# Western_Aero_2020.net
KiCad netlist of a schematic drawn in EAGLE
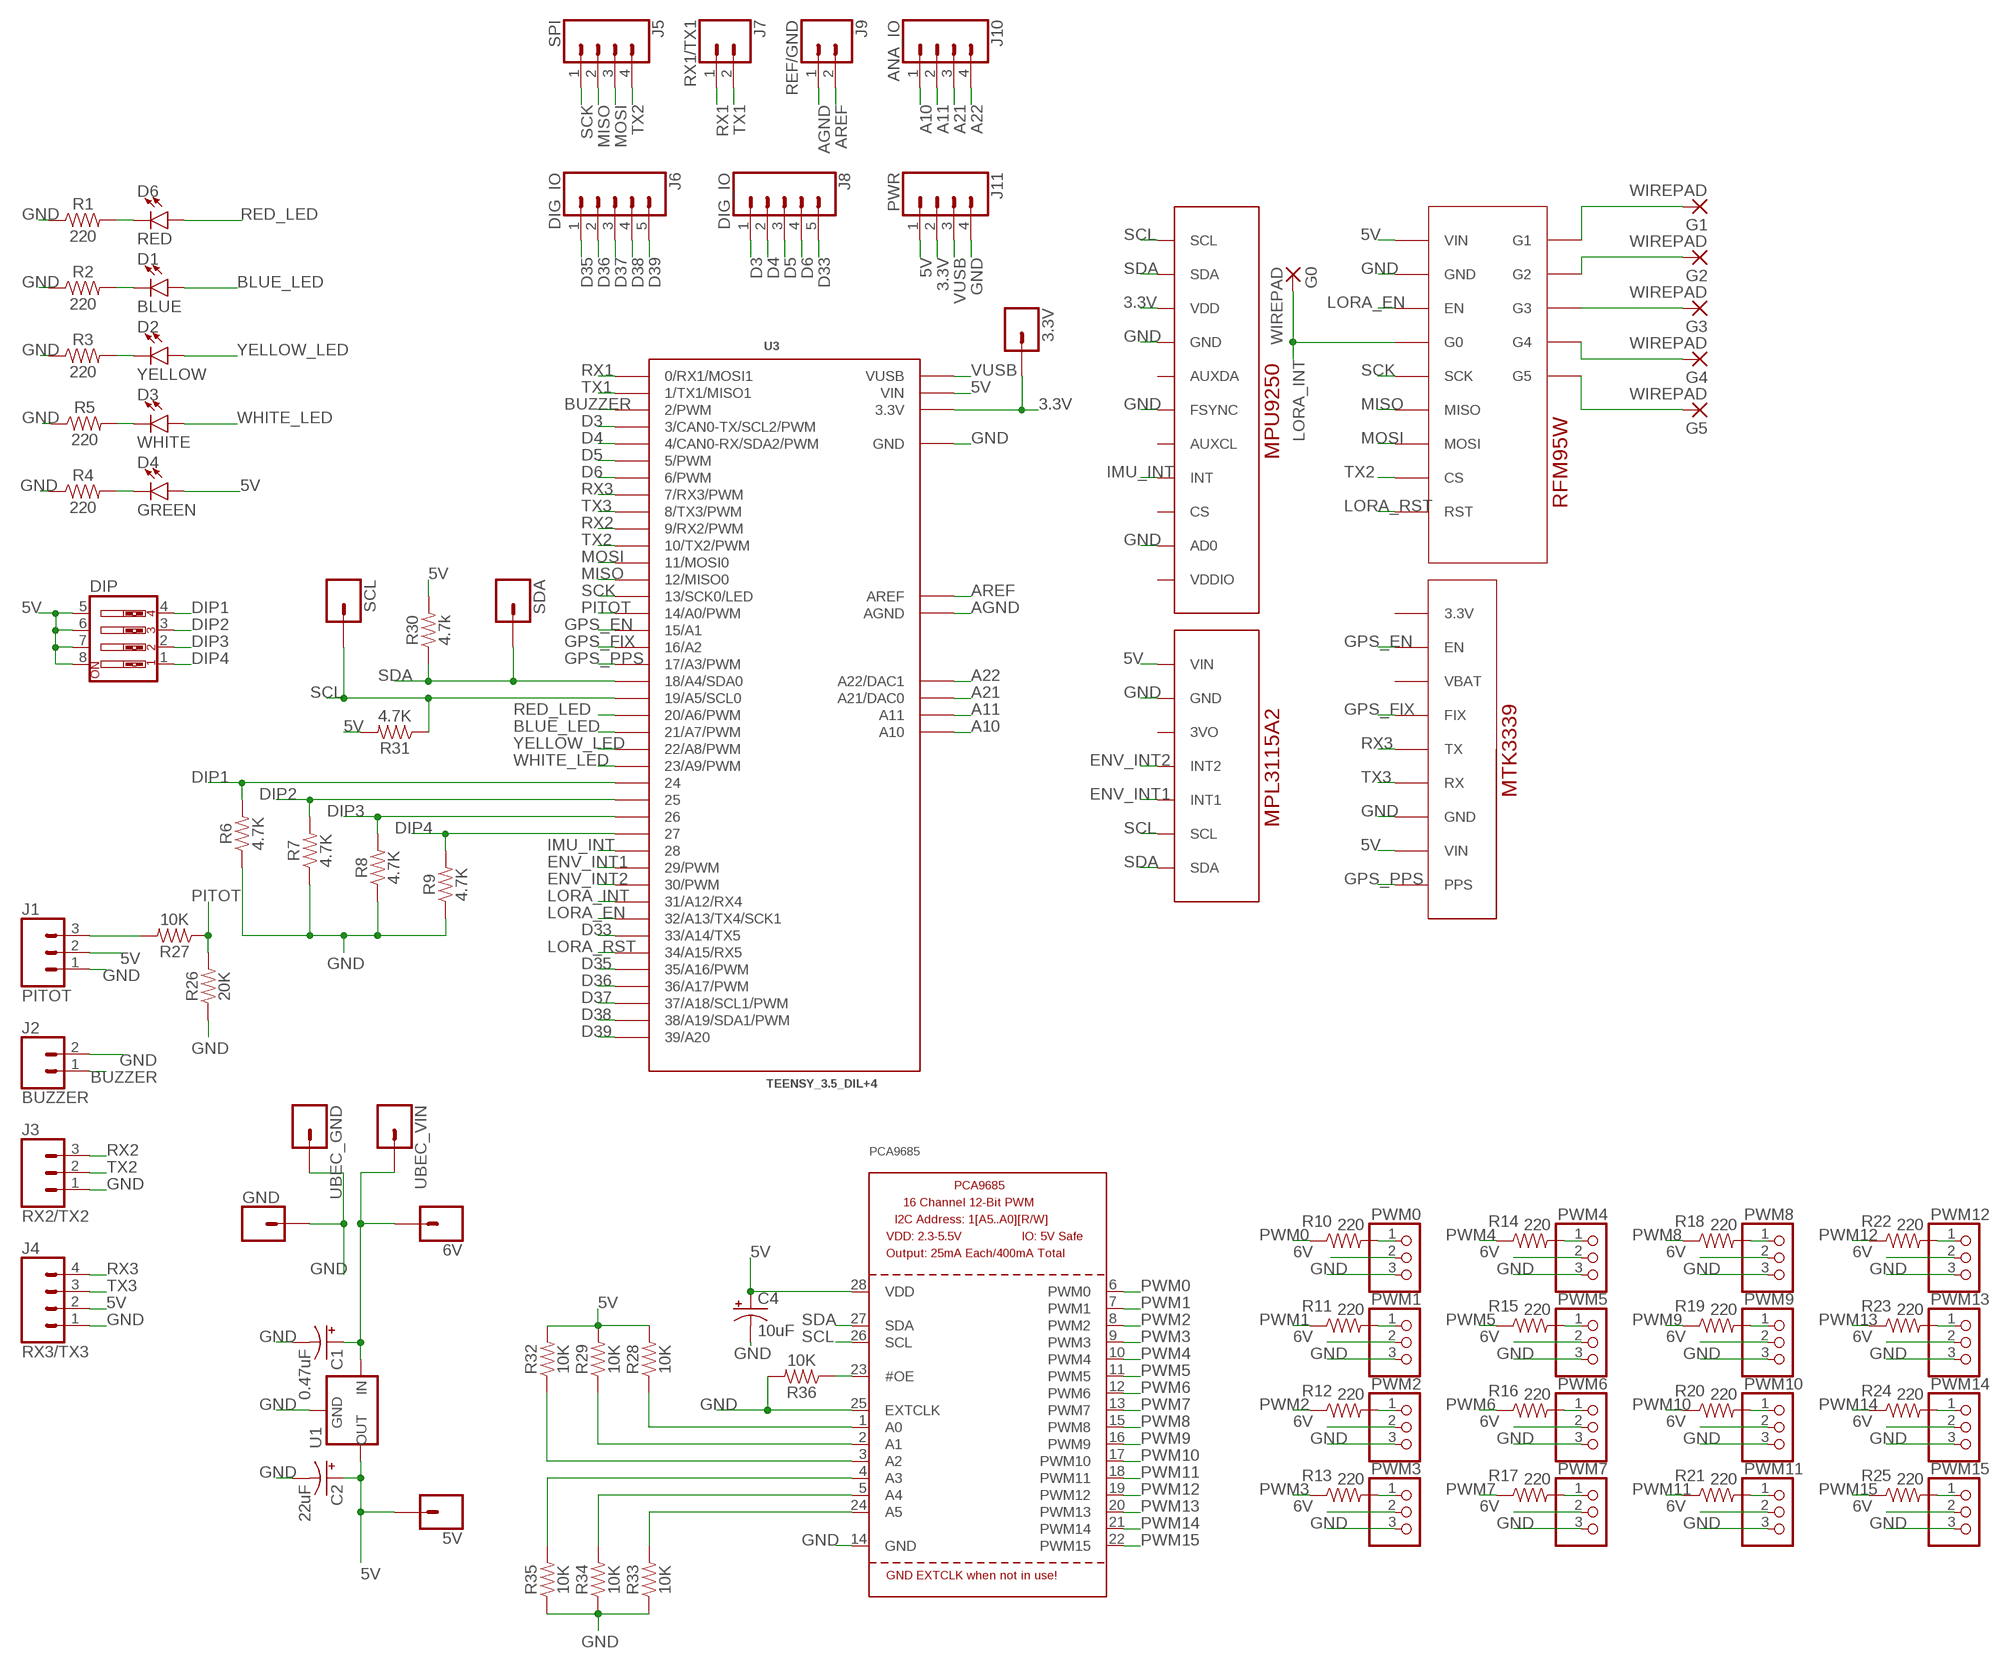
[diagram p0: schematic, sheet 1]

(export (version "E")
  (design (tool "Eeschema 10.0.6"))
  (components
    (comp (ref "3.3V")
      (value "CONN_01")
      (footprint "eagle-import:1X01")
      (libsource (lib "eagle-import") (part "CONN_01"))
    )
    (comp (ref "5V")
      (value "CONN_01")
      (footprint "eagle-import:1X01")
      (libsource (lib "eagle-import") (part "CONN_01"))
    )
    (comp (ref "6V")
      (value "CONN_01")
      (footprint "eagle-import:1X01")
      (libsource (lib "eagle-import") (part "CONN_01"))
    )
    (comp (ref "C1")
      (value "0.47uF")
      (footprint "eagle-import:CPOL-RADIAL-2.5MM-5MM")
      (libsource (lib "eagle-import") (part "10UF-POLAR-RADIAL-2.5MM-25V-20%"))
    )
    (comp (ref "C2")
      (value "22uF")
      (footprint "eagle-import:CPOL-RADIAL-2.5MM-5MM")
      (libsource (lib "eagle-import") (part "10UF-POLAR-RADIAL-2.5MM-25V-20%"))
    )
    (comp (ref "C4")
      (value "10uF")
      (footprint "eagle-import:CPOL-RADIAL-2.5MM-5MM")
      (libsource (lib "eagle-import") (part "10UF-POLAR-RADIAL-2.5MM-25V-20%"))
    )
    (comp (ref "D1")
      (value "BLUE")
      (footprint "eagle-import:LED_5MM")
      (libsource (lib "eagle-import") (part "LED5MM"))
    )
    (comp (ref "D2")
      (value "YELLOW")
      (footprint "eagle-import:LED_5MM")
      (libsource (lib "eagle-import") (part "LED5MM"))
    )
    (comp (ref "D3")
      (value "WHITE")
      (footprint "eagle-import:LED_5MM")
      (libsource (lib "eagle-import") (part "LED5MM"))
    )
    (comp (ref "D4")
      (value "GREEN")
      (footprint "eagle-import:LED_5MM")
      (libsource (lib "eagle-import") (part "LED5MM"))
    )
    (comp (ref "D6")
      (value "RED")
      (footprint "eagle-import:LED_5MM")
      (libsource (lib "eagle-import") (part "LED5MM"))
    )
    (comp (ref "DIP")
      (value "SW_DIP-4")
      (footprint "eagle-import:EDG-04")
      (libsource (lib "eagle-import") (part "SW_DIP-4"))
    )
    (comp (ref "G0")
      (value "WIREPAD")
      (footprint "eagle-import:2,15_1,0")
      (libsource (lib "eagle-import") (part "WIREPAD2,15/1,0"))
    )
    (comp (ref "G1")
      (value "WIREPAD")
      (footprint "eagle-import:2,15_1,0")
      (libsource (lib "eagle-import") (part "WIREPAD2,15/1,0"))
    )
    (comp (ref "G2")
      (value "WIREPAD")
      (footprint "eagle-import:2,15_1,0")
      (libsource (lib "eagle-import") (part "WIREPAD2,15/1,0"))
    )
    (comp (ref "G3")
      (value "WIREPAD")
      (footprint "eagle-import:2,15_1,0")
      (libsource (lib "eagle-import") (part "WIREPAD2,15/1,0"))
    )
    (comp (ref "G4")
      (value "WIREPAD")
      (footprint "eagle-import:2,15_1,0")
      (libsource (lib "eagle-import") (part "WIREPAD2,15/1,0"))
    )
    (comp (ref "G5")
      (value "WIREPAD")
      (footprint "eagle-import:2,15_1,0")
      (libsource (lib "eagle-import") (part "WIREPAD2,15/1,0"))
    )
    (comp (ref "GND")
      (value "CONN_01")
      (footprint "eagle-import:1X01")
      (libsource (lib "eagle-import") (part "CONN_01"))
    )
    (comp (ref "J1")
      (value "PITOT")
      (footprint "eagle-import:1X03")
      (libsource (lib "eagle-import") (part "CONN_03"))
    )
    (comp (ref "J2")
      (value "BUZZER")
      (footprint "eagle-import:1X02")
      (libsource (lib "eagle-import") (part "CONN_02"))
    )
    (comp (ref "J3")
      (value "RX2/TX2")
      (footprint "eagle-import:1X03")
      (libsource (lib "eagle-import") (part "CONN_03"))
    )
    (comp (ref "J4")
      (value "RX3/TX3")
      (footprint "eagle-import:1X04")
      (libsource (lib "eagle-import") (part "CONN_04"))
    )
    (comp (ref "J5")
      (value "SPI")
      (footprint "eagle-import:1X04")
      (libsource (lib "eagle-import") (part "CONN_04"))
    )
    (comp (ref "J6")
      (value "DIG_IO")
      (footprint "eagle-import:1X05")
      (libsource (lib "eagle-import") (part "CONN_05"))
    )
    (comp (ref "J7")
      (value "RX1/TX1")
      (footprint "eagle-import:1X02")
      (libsource (lib "eagle-import") (part "CONN_02"))
    )
    (comp (ref "J8")
      (value "DIG_IO")
      (footprint "eagle-import:1X05")
      (libsource (lib "eagle-import") (part "CONN_05"))
    )
    (comp (ref "J9")
      (value "REF/GND")
      (footprint "eagle-import:1X02")
      (libsource (lib "eagle-import") (part "CONN_02"))
    )
    (comp (ref "J10")
      (value "ANA_IO")
      (footprint "eagle-import:1X04")
      (libsource (lib "eagle-import") (part "CONN_04"))
    )
    (comp (ref "J11")
      (value "PWR")
      (footprint "eagle-import:1X04")
      (libsource (lib "eagle-import") (part "CONN_04"))
    )
    (comp (ref "JP1")
      (value "PWM0")
      (footprint "eagle-import:1X03")
      (libsource (lib "eagle-import") (part "PINHD-1X3"))
    )
    (comp (ref "JP2")
      (value "PWM1")
      (footprint "eagle-import:1X03")
      (libsource (lib "eagle-import") (part "PINHD-1X3"))
    )
    (comp (ref "JP3")
      (value "PWM2")
      (footprint "eagle-import:1X03")
      (libsource (lib "eagle-import") (part "PINHD-1X3"))
    )
    (comp (ref "JP4")
      (value "PWM3")
      (footprint "eagle-import:1X03")
      (libsource (lib "eagle-import") (part "PINHD-1X3"))
    )
    (comp (ref "JP5")
      (value "PWM4")
      (footprint "eagle-import:1X03")
      (libsource (lib "eagle-import") (part "PINHD-1X3"))
    )
    (comp (ref "JP6")
      (value "PWM5")
      (footprint "eagle-import:1X03")
      (libsource (lib "eagle-import") (part "PINHD-1X3"))
    )
    (comp (ref "JP7")
      (value "PWM6")
      (footprint "eagle-import:1X03")
      (libsource (lib "eagle-import") (part "PINHD-1X3"))
    )
    (comp (ref "JP8")
      (value "PWM7")
      (footprint "eagle-import:1X03")
      (libsource (lib "eagle-import") (part "PINHD-1X3"))
    )
    (comp (ref "JP9")
      (value "PWM8")
      (footprint "eagle-import:1X03")
      (libsource (lib "eagle-import") (part "PINHD-1X3"))
    )
    (comp (ref "JP10")
      (value "PWM9")
      (footprint "eagle-import:1X03")
      (libsource (lib "eagle-import") (part "PINHD-1X3"))
    )
    (comp (ref "JP11")
      (value "PWM10")
      (footprint "eagle-import:1X03")
      (libsource (lib "eagle-import") (part "PINHD-1X3"))
    )
    (comp (ref "JP12")
      (value "PWM11")
      (footprint "eagle-import:1X03")
      (libsource (lib "eagle-import") (part "PINHD-1X3"))
    )
    (comp (ref "JP13")
      (value "PWM12")
      (footprint "eagle-import:1X03")
      (libsource (lib "eagle-import") (part "PINHD-1X3"))
    )
    (comp (ref "JP14")
      (value "PWM13")
      (footprint "eagle-import:1X03")
      (libsource (lib "eagle-import") (part "PINHD-1X3"))
    )
    (comp (ref "JP15")
      (value "PWM14")
      (footprint "eagle-import:1X03")
      (libsource (lib "eagle-import") (part "PINHD-1X3"))
    )
    (comp (ref "JP16")
      (value "PWM15")
      (footprint "eagle-import:1X03")
      (libsource (lib "eagle-import") (part "PINHD-1X3"))
    )
    (comp (ref "PCA9685")
      (value "PCA9685")
      (footprint "eagle-import:TSSOP28")
      (libsource (lib "eagle-import") (part "PCA9685"))
    )
    (comp (ref "R1")
      (value "220")
      (footprint "eagle-import:AXIAL-0.3")
      (libsource (lib "eagle-import") (part "330OHM-HORIZ-1/10W-5%"))
    )
    (comp (ref "R2")
      (value "220")
      (footprint "eagle-import:AXIAL-0.3")
      (libsource (lib "eagle-import") (part "330OHM-HORIZ-1/10W-5%"))
    )
    (comp (ref "R3")
      (value "220")
      (footprint "eagle-import:AXIAL-0.3")
      (libsource (lib "eagle-import") (part "330OHM-HORIZ-1/10W-5%"))
    )
    (comp (ref "R4")
      (value "220")
      (footprint "eagle-import:AXIAL-0.3")
      (libsource (lib "eagle-import") (part "330OHM-HORIZ-1/10W-5%"))
    )
    (comp (ref "R5")
      (value "220")
      (footprint "eagle-import:AXIAL-0.3")
      (libsource (lib "eagle-import") (part "330OHM-HORIZ-1/10W-5%"))
    )
    (comp (ref "R6")
      (value "4.7K")
      (footprint "eagle-import:AXIAL-0.3")
      (libsource (lib "eagle-import") (part "330OHM-HORIZ-1/10W-5%"))
    )
    (comp (ref "R7")
      (value "4.7K")
      (footprint "eagle-import:AXIAL-0.3")
      (libsource (lib "eagle-import") (part "330OHM-HORIZ-1/10W-5%"))
    )
    (comp (ref "R8")
      (value "4.7K")
      (footprint "eagle-import:AXIAL-0.3")
      (libsource (lib "eagle-import") (part "330OHM-HORIZ-1/10W-5%"))
    )
    (comp (ref "R9")
      (value "4.7K")
      (footprint "eagle-import:AXIAL-0.3")
      (libsource (lib "eagle-import") (part "330OHM-HORIZ-1/10W-5%"))
    )
    (comp (ref "R10")
      (value "220")
      (footprint "eagle-import:AXIAL-0.3")
      (libsource (lib "eagle-import") (part "330OHM-HORIZ-1/10W-5%"))
    )
    (comp (ref "R11")
      (value "220")
      (footprint "eagle-import:AXIAL-0.3")
      (libsource (lib "eagle-import") (part "330OHM-HORIZ-1/10W-5%"))
    )
    (comp (ref "R12")
      (value "220")
      (footprint "eagle-import:AXIAL-0.3")
      (libsource (lib "eagle-import") (part "330OHM-HORIZ-1/10W-5%"))
    )
    (comp (ref "R13")
      (value "220")
      (footprint "eagle-import:AXIAL-0.3")
      (libsource (lib "eagle-import") (part "330OHM-HORIZ-1/10W-5%"))
    )
    (comp (ref "R14")
      (value "220")
      (footprint "eagle-import:AXIAL-0.3")
      (libsource (lib "eagle-import") (part "330OHM-HORIZ-1/10W-5%"))
    )
    (comp (ref "R15")
      (value "220")
      (footprint "eagle-import:AXIAL-0.3")
      (libsource (lib "eagle-import") (part "330OHM-HORIZ-1/10W-5%"))
    )
    (comp (ref "R16")
      (value "220")
      (footprint "eagle-import:AXIAL-0.3")
      (libsource (lib "eagle-import") (part "330OHM-HORIZ-1/10W-5%"))
    )
    (comp (ref "R17")
      (value "220")
      (footprint "eagle-import:AXIAL-0.3")
      (libsource (lib "eagle-import") (part "330OHM-HORIZ-1/10W-5%"))
    )
    (comp (ref "R18")
      (value "220")
      (footprint "eagle-import:AXIAL-0.3")
      (libsource (lib "eagle-import") (part "330OHM-HORIZ-1/10W-5%"))
    )
    (comp (ref "R19")
      (value "220")
      (footprint "eagle-import:AXIAL-0.3")
      (libsource (lib "eagle-import") (part "330OHM-HORIZ-1/10W-5%"))
    )
    (comp (ref "R20")
      (value "220")
      (footprint "eagle-import:AXIAL-0.3")
      (libsource (lib "eagle-import") (part "330OHM-HORIZ-1/10W-5%"))
    )
    (comp (ref "R21")
      (value "220")
      (footprint "eagle-import:AXIAL-0.3")
      (libsource (lib "eagle-import") (part "330OHM-HORIZ-1/10W-5%"))
    )
    (comp (ref "R22")
      (value "220")
      (footprint "eagle-import:AXIAL-0.3")
      (libsource (lib "eagle-import") (part "330OHM-HORIZ-1/10W-5%"))
    )
    (comp (ref "R23")
      (value "220")
      (footprint "eagle-import:AXIAL-0.3")
      (libsource (lib "eagle-import") (part "330OHM-HORIZ-1/10W-5%"))
    )
    (comp (ref "R24")
      (value "220")
      (footprint "eagle-import:AXIAL-0.3")
      (libsource (lib "eagle-import") (part "330OHM-HORIZ-1/10W-5%"))
    )
    (comp (ref "R25")
      (value "220")
      (footprint "eagle-import:AXIAL-0.3")
      (libsource (lib "eagle-import") (part "330OHM-HORIZ-1/10W-5%"))
    )
    (comp (ref "R26")
      (value "20K")
      (footprint "eagle-import:AXIAL-0.3")
      (libsource (lib "eagle-import") (part "330OHM-HORIZ-1/10W-5%"))
    )
    (comp (ref "R27")
      (value "10K")
      (footprint "eagle-import:AXIAL-0.3")
      (libsource (lib "eagle-import") (part "330OHM-HORIZ-1/10W-5%"))
    )
    (comp (ref "R28")
      (value "10K")
      (footprint "eagle-import:AXIAL-0.3")
      (libsource (lib "eagle-import") (part "330OHM-HORIZ-1/10W-5%"))
    )
    (comp (ref "R29")
      (value "10K")
      (footprint "eagle-import:AXIAL-0.3")
      (libsource (lib "eagle-import") (part "330OHM-HORIZ-1/10W-5%"))
    )
    (comp (ref "R30")
      (value "4.7k")
      (footprint "eagle-import:AXIAL-0.3")
      (libsource (lib "eagle-import") (part "330OHM-HORIZ-1/10W-5%"))
    )
    (comp (ref "R31")
      (value "4.7K")
      (footprint "eagle-import:AXIAL-0.3")
      (libsource (lib "eagle-import") (part "330OHM-HORIZ-1/10W-5%"))
    )
    (comp (ref "R32")
      (value "10K")
      (footprint "eagle-import:AXIAL-0.3")
      (libsource (lib "eagle-import") (part "330OHM-HORIZ-1/10W-5%"))
    )
    (comp (ref "R33")
      (value "10K")
      (footprint "eagle-import:AXIAL-0.3")
      (libsource (lib "eagle-import") (part "330OHM-HORIZ-1/10W-5%"))
    )
    (comp (ref "R34")
      (value "10K")
      (footprint "eagle-import:AXIAL-0.3")
      (libsource (lib "eagle-import") (part "330OHM-HORIZ-1/10W-5%"))
    )
    (comp (ref "R35")
      (value "10K")
      (footprint "eagle-import:AXIAL-0.3")
      (libsource (lib "eagle-import") (part "330OHM-HORIZ-1/10W-5%"))
    )
    (comp (ref "R36")
      (value "10K")
      (footprint "eagle-import:AXIAL-0.3")
      (libsource (lib "eagle-import") (part "330OHM-HORIZ-1/10W-5%"))
    )
    (comp (ref "SCL")
      (value "CONN_01")
      (footprint "eagle-import:1X01")
      (libsource (lib "eagle-import") (part "CONN_01"))
    )
    (comp (ref "SDA")
      (value "CONN_01")
      (footprint "eagle-import:1X01")
      (libsource (lib "eagle-import") (part "CONN_01"))
    )
    (comp (ref "U1")
      (value "V_REG_78XXSINK")
      (footprint "eagle-import:TO220-IGO")
      (libsource (lib "eagle-import") (part "V_REG_78XXSINK"))
    )
    (comp (ref "U3")
      (value "TEENSY_3.5_DIL+4")
      (footprint "eagle-import:TEENSY_3.5_DIL+4")
      (libsource (lib "eagle-import") (part "TEENSY_3.5_DIL+4"))
    )
    (comp (ref "U5")
      (value "SPARKFUN_MPU9250_IMU")
      (footprint "eagle-import:SPARKFUN_MPU9250_IMU")
      (libsource (lib "eagle-import") (part "SPARKFUN_MPU9250_IMU"))
    )
    (comp (ref "U6")
      (value "ADAFRUIT_MPL3115A2_BAROMETER")
      (footprint "eagle-import:ADAFRUIT_MPL3115A2_BAROMETER")
      (libsource (lib "eagle-import") (part "ADAFRUIT_MPL3115A2_BAROMETER"))
    )
    (comp (ref "U8")
      (value "ADAFRUIT_RFM95W_LORA_RADIO")
      (footprint "eagle-import:ADAFRUIT_RFM95W_LORA_RADIO")
      (libsource (lib "eagle-import") (part "ADAFRUIT_RFM95W_LORA_RADIO"))
    )
    (comp (ref "U9")
      (value "ADAFRUIT_MTK3339_GPS")
      (footprint "eagle-import:ADAFRUIT_MTK3339_GPS")
      (libsource (lib "eagle-import") (part "ADAFRUIT_MTK3339_GPS"))
    )
    (comp (ref "UBEC_GND")
      (value "CONN_01")
      (footprint "eagle-import:1X01")
      (libsource (lib "eagle-import") (part "CONN_01"))
    )
    (comp (ref "UBEC_VIN")
      (value "CONN_01")
      (footprint "eagle-import:1X01")
      (libsource (lib "eagle-import") (part "CONN_01"))
    )
  )
  (nets
    (net (code "1") (name "/3.3V") (class "Default")
      (node (ref "3.3V") (pin "1") (pinfunction "1_1") (pintype "passive"))
      (node (ref "J11") (pin "2") (pinfunction "2_2") (pintype "passive"))
      (node (ref "U3") (pin "3.3V") (pinfunction "3.3V_3.3V") (pintype "power_in"))
      (node (ref "U3") (pin "3.3V3") (pinfunction "3.3V_3.3V3") (pintype "power_in"))
      (node (ref "U5") (pin "VDD") (pinfunction "VDD_VDD") (pintype "bidirectional"))
    )
    (net (code "2") (name "/5V") (class "Default")
      (node (ref "5V") (pin "1") (pinfunction "1_1") (pintype "passive"))
      (node (ref "C2") (pin "1") (pinfunction "+_1") (pintype "passive"))
      (node (ref "C4") (pin "1") (pinfunction "+_1") (pintype "passive"))
      (node (ref "D4") (pin "A") (pinfunction "A_A") (pintype "passive"))
      (node (ref "DIP") (pin "5") (pinfunction "5_5") (pintype "passive"))
      (node (ref "DIP") (pin "6") (pinfunction "6_6") (pintype "passive"))
      (node (ref "DIP") (pin "7") (pinfunction "7_7") (pintype "passive"))
      (node (ref "DIP") (pin "8") (pinfunction "8_8") (pintype "passive"))
      (node (ref "J1") (pin "2") (pinfunction "2_2") (pintype "passive"))
      (node (ref "J11") (pin "1") (pinfunction "1_1") (pintype "passive"))
      (node (ref "J4") (pin "2") (pinfunction "2_2") (pintype "passive"))
      (node (ref "PCA9685") (pin "28") (pinfunction "VDD_28") (pintype "power_in"))
      (node (ref "R28") (pin "P$2") (pinfunction "2_P$2") (pintype "passive"))
      (node (ref "R29") (pin "P$2") (pinfunction "2_P$2") (pintype "passive"))
      (node (ref "R30") (pin "P$2") (pinfunction "2_P$2") (pintype "passive"))
      (node (ref "R31") (pin "P$2") (pinfunction "2_P$2") (pintype "passive"))
      (node (ref "R32") (pin "P$2") (pinfunction "2_P$2") (pintype "passive"))
      (node (ref "U1") (pin "OUT") (pinfunction "OUT_OUT") (pintype "passive"))
      (node (ref "U3") (pin "VIN") (pinfunction "VIN_VIN") (pintype "power_in"))
      (node (ref "U6") (pin "VIN") (pinfunction "VIN_VIN") (pintype "bidirectional"))
      (node (ref "U8") (pin "1") (pinfunction "VIN_1") (pintype "bidirectional"))
      (node (ref "U9") (pin "VIN") (pinfunction "VIN_VIN") (pintype "bidirectional"))
    )
    (net (code "3") (name "/6V") (class "Default")
      (node (ref "6V") (pin "1") (pinfunction "1_1") (pintype "passive"))
      (node (ref "C1") (pin "1") (pinfunction "+_1") (pintype "passive"))
      (node (ref "JP1") (pin "2") (pinfunction "2_2") (pintype "passive"))
      (node (ref "JP10") (pin "2") (pinfunction "2_2") (pintype "passive"))
      (node (ref "JP11") (pin "2") (pinfunction "2_2") (pintype "passive"))
      (node (ref "JP12") (pin "2") (pinfunction "2_2") (pintype "passive"))
      (node (ref "JP13") (pin "2") (pinfunction "2_2") (pintype "passive"))
      (node (ref "JP14") (pin "2") (pinfunction "2_2") (pintype "passive"))
      (node (ref "JP15") (pin "2") (pinfunction "2_2") (pintype "passive"))
      (node (ref "JP16") (pin "2") (pinfunction "2_2") (pintype "passive"))
      (node (ref "JP2") (pin "2") (pinfunction "2_2") (pintype "passive"))
      (node (ref "JP3") (pin "2") (pinfunction "2_2") (pintype "passive"))
      (node (ref "JP4") (pin "2") (pinfunction "2_2") (pintype "passive"))
      (node (ref "JP5") (pin "2") (pinfunction "2_2") (pintype "passive"))
      (node (ref "JP6") (pin "2") (pinfunction "2_2") (pintype "passive"))
      (node (ref "JP7") (pin "2") (pinfunction "2_2") (pintype "passive"))
      (node (ref "JP8") (pin "2") (pinfunction "2_2") (pintype "passive"))
      (node (ref "JP9") (pin "2") (pinfunction "2_2") (pintype "passive"))
      (node (ref "U1") (pin "IN") (pinfunction "IN_IN") (pintype "input"))
      (node (ref "UBEC_VIN") (pin "1") (pinfunction "1_1") (pintype "passive"))
    )
    (net (code "4") (name "/A10") (class "Default")
      (node (ref "J10") (pin "1") (pinfunction "1_1") (pintype "passive"))
      (node (ref "U3") (pin "A10") (pinfunction "A10_A10") (pintype "bidirectional"))
    )
    (net (code "5") (name "/A11") (class "Default")
      (node (ref "J10") (pin "2") (pinfunction "2_2") (pintype "passive"))
      (node (ref "U3") (pin "A11") (pinfunction "A11_A11") (pintype "bidirectional"))
    )
    (net (code "6") (name "/A21") (class "Default")
      (node (ref "J10") (pin "3") (pinfunction "3_3") (pintype "passive"))
      (node (ref "U3") (pin "A21") (pinfunction "A21/DAC0_A21") (pintype "bidirectional"))
    )
    (net (code "7") (name "/A22") (class "Default")
      (node (ref "J10") (pin "4") (pinfunction "4_4") (pintype "passive"))
      (node (ref "U3") (pin "A22") (pinfunction "A22/DAC1_A22") (pintype "bidirectional"))
    )
    (net (code "8") (name "/AGND") (class "Default")
      (node (ref "J9") (pin "1") (pinfunction "1_1") (pintype "passive"))
      (node (ref "U3") (pin "AGND") (pinfunction "AGND_AGND") (pintype "power_in"))
    )
    (net (code "9") (name "/AREF") (class "Default")
      (node (ref "J9") (pin "2") (pinfunction "2_2") (pintype "passive"))
      (node (ref "U3") (pin "AREF") (pinfunction "AREF_AREF") (pintype "power_in"))
    )
    (net (code "10") (name "/BLUE_LED") (class "Default")
      (node (ref "D1") (pin "A") (pinfunction "A_A") (pintype "passive"))
      (node (ref "U3") (pin "21/A7") (pinfunction "21/A7/PWM_21/A7") (pintype "bidirectional"))
    )
    (net (code "11") (name "/BUZZER") (class "Default")
      (node (ref "J2") (pin "1") (pinfunction "1_1") (pintype "passive"))
      (node (ref "U3") (pin "2") (pinfunction "2/PWM_2") (pintype "bidirectional"))
    )
    (net (code "12") (name "/D3") (class "Default")
      (node (ref "J8") (pin "1") (pinfunction "1_1") (pintype "passive"))
      (node (ref "U3") (pin "3") (pinfunction "3/CAN0-TX/SCL2/PWM_3") (pintype "bidirectional"))
    )
    (net (code "13") (name "/D4") (class "Default")
      (node (ref "J8") (pin "2") (pinfunction "2_2") (pintype "passive"))
      (node (ref "U3") (pin "4") (pinfunction "4/CAN0-RX/SDA2/PWM_4") (pintype "bidirectional"))
    )
    (net (code "14") (name "/D5") (class "Default")
      (node (ref "J8") (pin "3") (pinfunction "3_3") (pintype "passive"))
      (node (ref "U3") (pin "5") (pinfunction "5/PWM_5") (pintype "bidirectional"))
    )
    (net (code "15") (name "/D6") (class "Default")
      (node (ref "J8") (pin "4") (pinfunction "4_4") (pintype "passive"))
      (node (ref "U3") (pin "6") (pinfunction "6/PWM_6") (pintype "bidirectional"))
    )
    (net (code "16") (name "/D33") (class "Default")
      (node (ref "J8") (pin "5") (pinfunction "5_5") (pintype "passive"))
      (node (ref "U3") (pin "33/A14") (pinfunction "33/A14/TX5_33/A14") (pintype "bidirectional"))
    )
    (net (code "17") (name "/D35") (class "Default")
      (node (ref "J6") (pin "1") (pinfunction "1_1") (pintype "passive"))
      (node (ref "U3") (pin "35/A16") (pinfunction "35/A16/PWM_35/A16") (pintype "bidirectional"))
    )
    (net (code "18") (name "/D36") (class "Default")
      (node (ref "J6") (pin "2") (pinfunction "2_2") (pintype "passive"))
      (node (ref "U3") (pin "36/A17") (pinfunction "36/A17/PWM_36/A17") (pintype "bidirectional"))
    )
    (net (code "19") (name "/D37") (class "Default")
      (node (ref "J6") (pin "3") (pinfunction "3_3") (pintype "passive"))
      (node (ref "U3") (pin "37/A18") (pinfunction "37/A18/SCL1/PWM_37/A18") (pintype "bidirectional"))
    )
    (net (code "20") (name "/D38") (class "Default")
      (node (ref "J6") (pin "4") (pinfunction "4_4") (pintype "passive"))
      (node (ref "U3") (pin "38/A19") (pinfunction "38/A19/SDA1/PWM_38/A19") (pintype "bidirectional"))
    )
    (net (code "21") (name "/D39") (class "Default")
      (node (ref "J6") (pin "5") (pinfunction "5_5") (pintype "passive"))
      (node (ref "U3") (pin "39/A20") (pinfunction "39/A20_39/A20") (pintype "bidirectional"))
    )
    (net (code "22") (name "/DIP1") (class "Default")
      (node (ref "DIP") (pin "4") (pinfunction "4_4") (pintype "passive"))
      (node (ref "R6") (pin "P$2") (pinfunction "2_P$2") (pintype "passive"))
      (node (ref "U3") (pin "24") (pinfunction "24_24") (pintype "bidirectional"))
    )
    (net (code "23") (name "/DIP2") (class "Default")
      (node (ref "DIP") (pin "3") (pinfunction "3_3") (pintype "passive"))
      (node (ref "R7") (pin "P$2") (pinfunction "2_P$2") (pintype "passive"))
      (node (ref "U3") (pin "25") (pinfunction "25_25") (pintype "bidirectional"))
    )
    (net (code "24") (name "/DIP3") (class "Default")
      (node (ref "DIP") (pin "2") (pinfunction "2_2") (pintype "passive"))
      (node (ref "R8") (pin "P$2") (pinfunction "2_P$2") (pintype "passive"))
      (node (ref "U3") (pin "26") (pinfunction "26_26") (pintype "bidirectional"))
    )
    (net (code "25") (name "/DIP4") (class "Default")
      (node (ref "DIP") (pin "1") (pinfunction "1_1") (pintype "passive"))
      (node (ref "R9") (pin "P$2") (pinfunction "2_P$2") (pintype "passive"))
      (node (ref "U3") (pin "27") (pinfunction "27_27") (pintype "bidirectional"))
    )
    (net (code "26") (name "/ENV_INT1") (class "Default")
      (node (ref "U3") (pin "29") (pinfunction "29/PWM_29") (pintype "bidirectional"))
      (node (ref "U6") (pin "INT1") (pinfunction "INT1_INT1") (pintype "bidirectional"))
    )
    (net (code "27") (name "/ENV_INT2") (class "Default")
      (node (ref "U3") (pin "30") (pinfunction "30/PWM_30") (pintype "bidirectional"))
      (node (ref "U6") (pin "INT2") (pinfunction "INT2_INT2") (pintype "bidirectional"))
    )
    (net (code "28") (name "/GND") (class "Default")
      (node (ref "C1") (pin "2") (pinfunction "-_2") (pintype "passive"))
      (node (ref "C2") (pin "2") (pinfunction "-_2") (pintype "passive"))
      (node (ref "C4") (pin "2") (pinfunction "-_2") (pintype "passive"))
      (node (ref "GND") (pin "1") (pinfunction "1_1") (pintype "passive"))
      (node (ref "J1") (pin "1") (pinfunction "1_1") (pintype "passive"))
      (node (ref "J11") (pin "4") (pinfunction "4_4") (pintype "passive"))
      (node (ref "J2") (pin "2") (pinfunction "2_2") (pintype "passive"))
      (node (ref "J3") (pin "1") (pinfunction "1_1") (pintype "passive"))
      (node (ref "J4") (pin "1") (pinfunction "1_1") (pintype "passive"))
      (node (ref "JP1") (pin "3") (pinfunction "3_3") (pintype "passive"))
      (node (ref "JP10") (pin "3") (pinfunction "3_3") (pintype "passive"))
      (node (ref "JP11") (pin "3") (pinfunction "3_3") (pintype "passive"))
      (node (ref "JP12") (pin "3") (pinfunction "3_3") (pintype "passive"))
      (node (ref "JP13") (pin "3") (pinfunction "3_3") (pintype "passive"))
      (node (ref "JP14") (pin "3") (pinfunction "3_3") (pintype "passive"))
      (node (ref "JP15") (pin "3") (pinfunction "3_3") (pintype "passive"))
      (node (ref "JP16") (pin "3") (pinfunction "3_3") (pintype "passive"))
      (node (ref "JP2") (pin "3") (pinfunction "3_3") (pintype "passive"))
      (node (ref "JP3") (pin "3") (pinfunction "3_3") (pintype "passive"))
      (node (ref "JP4") (pin "3") (pinfunction "3_3") (pintype "passive"))
      (node (ref "JP5") (pin "3") (pinfunction "3_3") (pintype "passive"))
      (node (ref "JP6") (pin "3") (pinfunction "3_3") (pintype "passive"))
      (node (ref "JP7") (pin "3") (pinfunction "3_3") (pintype "passive"))
      (node (ref "JP8") (pin "3") (pinfunction "3_3") (pintype "passive"))
      (node (ref "JP9") (pin "3") (pinfunction "3_3") (pintype "passive"))
      (node (ref "PCA9685") (pin "14") (pinfunction "GND_14") (pintype "power_in"))
      (node (ref "PCA9685") (pin "25") (pinfunction "EXTCLK_25") (pintype "input"))
      (node (ref "R1") (pin "P$1") (pinfunction "1_P$1") (pintype "passive"))
      (node (ref "R2") (pin "P$1") (pinfunction "1_P$1") (pintype "passive"))
      (node (ref "R26") (pin "P$1") (pinfunction "1_P$1") (pintype "passive"))
      (node (ref "R3") (pin "P$1") (pinfunction "1_P$1") (pintype "passive"))
      (node (ref "R33") (pin "P$1") (pinfunction "1_P$1") (pintype "passive"))
      (node (ref "R34") (pin "P$1") (pinfunction "1_P$1") (pintype "passive"))
      (node (ref "R35") (pin "P$1") (pinfunction "1_P$1") (pintype "passive"))
      (node (ref "R36") (pin "P$2") (pinfunction "2_P$2") (pintype "passive"))
      (node (ref "R4") (pin "P$1") (pinfunction "1_P$1") (pintype "passive"))
      (node (ref "R5") (pin "P$1") (pinfunction "1_P$1") (pintype "passive"))
      (node (ref "R6") (pin "P$1") (pinfunction "1_P$1") (pintype "passive"))
      (node (ref "R7") (pin "P$1") (pinfunction "1_P$1") (pintype "passive"))
      (node (ref "R8") (pin "P$1") (pinfunction "1_P$1") (pintype "passive"))
      (node (ref "R9") (pin "P$1") (pinfunction "1_P$1") (pintype "passive"))
      (node (ref "U1") (pin "GND") (pinfunction "GND_GND") (pintype "input"))
      (node (ref "U3") (pin "GND") (pinfunction "GND_GND") (pintype "power_in"))
      (node (ref "U3") (pin "GND1") (pinfunction "GND_GND1") (pintype "power_in"))
      (node (ref "U5") (pin "AD0") (pinfunction "AD0_AD0") (pintype "bidirectional"))
      (node (ref "U5") (pin "FSYNC") (pinfunction "FSYNC_FSYNC") (pintype "bidirectional"))
      (node (ref "U5") (pin "GND") (pinfunction "GND_GND") (pintype "bidirectional"))
      (node (ref "U6") (pin "GND") (pinfunction "GND_GND") (pintype "bidirectional"))
      (node (ref "U8") (pin "2") (pinfunction "GND_2") (pintype "bidirectional"))
      (node (ref "U9") (pin "GND") (pinfunction "GND_GND") (pintype "bidirectional"))
      (node (ref "UBEC_GND") (pin "1") (pinfunction "1_1") (pintype "passive"))
    )
    (net (code "29") (name "/GPS_EN") (class "Default")
      (node (ref "U3") (pin "15/A1") (pinfunction "15/A1_15/A1") (pintype "bidirectional"))
      (node (ref "U9") (pin "EN") (pinfunction "EN_EN") (pintype "bidirectional"))
    )
    (net (code "30") (name "/GPS_FIX") (class "Default")
      (node (ref "U3") (pin "16/A2") (pinfunction "16/A2_16/A2") (pintype "bidirectional"))
      (node (ref "U9") (pin "FIX") (pinfunction "FIX_FIX") (pintype "bidirectional"))
    )
    (net (code "31") (name "/GPS_PPS") (class "Default")
      (node (ref "U3") (pin "17/A3") (pinfunction "17/A3/PWM_17/A3") (pintype "bidirectional"))
      (node (ref "U9") (pin "PPS") (pinfunction "PPS_PPS") (pintype "bidirectional"))
    )
    (net (code "32") (name "/IMU_INT") (class "Default")
      (node (ref "U3") (pin "28") (pinfunction "28_28") (pintype "bidirectional"))
      (node (ref "U5") (pin "INT") (pinfunction "INT_INT") (pintype "bidirectional"))
    )
    (net (code "33") (name "/LORA_EN") (class "Default")
      (node (ref "U3") (pin "32/A13") (pinfunction "32/A13/TX4/SCK1_32/A13") (pintype "bidirectional"))
      (node (ref "U8") (pin "3") (pinfunction "EN_3") (pintype "bidirectional"))
    )
    (net (code "34") (name "/LORA_INT") (class "Default")
      (node (ref "G0") (pin "1") (pinfunction "P_1") (pintype "passive"))
      (node (ref "U3") (pin "31/A12") (pinfunction "31/A12/RX4_31/A12") (pintype "bidirectional"))
      (node (ref "U8") (pin "4") (pinfunction "G0_4") (pintype "bidirectional"))
    )
    (net (code "35") (name "/LORA_RST") (class "Default")
      (node (ref "U3") (pin "34/A15") (pinfunction "34/A15/RX5_34/A15") (pintype "bidirectional"))
      (node (ref "U8") (pin "9") (pinfunction "RST_9") (pintype "bidirectional"))
    )
    (net (code "36") (name "/MISO") (class "Default")
      (node (ref "J5") (pin "2") (pinfunction "2_2") (pintype "passive"))
      (node (ref "U3") (pin "12") (pinfunction "12/MISO0_12") (pintype "bidirectional"))
      (node (ref "U8") (pin "6") (pinfunction "MISO_6") (pintype "bidirectional"))
    )
    (net (code "37") (name "/MOSI") (class "Default")
      (node (ref "J5") (pin "3") (pinfunction "3_3") (pintype "passive"))
      (node (ref "U3") (pin "11") (pinfunction "11/MOSI0_11") (pintype "bidirectional"))
      (node (ref "U8") (pin "7") (pinfunction "MOSI_7") (pintype "bidirectional"))
    )
    (net (code "38") (name "/PITOT") (class "Default")
      (node (ref "R26") (pin "P$2") (pinfunction "2_P$2") (pintype "passive"))
      (node (ref "R27") (pin "P$1") (pinfunction "1_P$1") (pintype "passive"))
      (node (ref "U3") (pin "14/A0") (pinfunction "14/A0/PWM_14/A0") (pintype "bidirectional"))
    )
    (net (code "39") (name "/PWM0") (class "Default")
      (node (ref "PCA9685") (pin "6") (pinfunction "PWM0_6") (pintype "output"))
      (node (ref "R10") (pin "P$1") (pinfunction "1_P$1") (pintype "passive"))
    )
    (net (code "40") (name "/PWM1") (class "Default")
      (node (ref "PCA9685") (pin "7") (pinfunction "PWM1_7") (pintype "output"))
      (node (ref "R11") (pin "P$1") (pinfunction "1_P$1") (pintype "passive"))
    )
    (net (code "41") (name "/PWM2") (class "Default")
      (node (ref "PCA9685") (pin "8") (pinfunction "PWM2_8") (pintype "output"))
      (node (ref "R12") (pin "P$1") (pinfunction "1_P$1") (pintype "passive"))
    )
    (net (code "42") (name "/PWM3") (class "Default")
      (node (ref "PCA9685") (pin "9") (pinfunction "PWM3_9") (pintype "output"))
      (node (ref "R13") (pin "P$1") (pinfunction "1_P$1") (pintype "passive"))
    )
    (net (code "43") (name "/PWM4") (class "Default")
      (node (ref "PCA9685") (pin "10") (pinfunction "PWM4_10") (pintype "output"))
      (node (ref "R14") (pin "P$1") (pinfunction "1_P$1") (pintype "passive"))
    )
    (net (code "44") (name "/PWM5") (class "Default")
      (node (ref "PCA9685") (pin "11") (pinfunction "PWM5_11") (pintype "output"))
      (node (ref "R15") (pin "P$1") (pinfunction "1_P$1") (pintype "passive"))
    )
    (net (code "45") (name "/PWM6") (class "Default")
      (node (ref "PCA9685") (pin "12") (pinfunction "PWM6_12") (pintype "output"))
      (node (ref "R16") (pin "P$1") (pinfunction "1_P$1") (pintype "passive"))
    )
    (net (code "46") (name "/PWM7") (class "Default")
      (node (ref "PCA9685") (pin "13") (pinfunction "PWM7_13") (pintype "output"))
      (node (ref "R17") (pin "P$1") (pinfunction "1_P$1") (pintype "passive"))
    )
    (net (code "47") (name "/PWM8") (class "Default")
      (node (ref "PCA9685") (pin "15") (pinfunction "PWM8_15") (pintype "output"))
      (node (ref "R18") (pin "P$1") (pinfunction "1_P$1") (pintype "passive"))
    )
    (net (code "48") (name "/PWM9") (class "Default")
      (node (ref "PCA9685") (pin "16") (pinfunction "PWM9_16") (pintype "output"))
      (node (ref "R19") (pin "P$1") (pinfunction "1_P$1") (pintype "passive"))
    )
    (net (code "49") (name "/PWM10") (class "Default")
      (node (ref "PCA9685") (pin "17") (pinfunction "PWM10_17") (pintype "output"))
      (node (ref "R20") (pin "P$1") (pinfunction "1_P$1") (pintype "passive"))
    )
    (net (code "50") (name "/PWM11") (class "Default")
      (node (ref "PCA9685") (pin "18") (pinfunction "PWM11_18") (pintype "output"))
      (node (ref "R21") (pin "P$1") (pinfunction "1_P$1") (pintype "passive"))
    )
    (net (code "51") (name "/PWM12") (class "Default")
      (node (ref "PCA9685") (pin "19") (pinfunction "PWM12_19") (pintype "output"))
      (node (ref "R22") (pin "P$1") (pinfunction "1_P$1") (pintype "passive"))
    )
    (net (code "52") (name "/PWM13") (class "Default")
      (node (ref "PCA9685") (pin "20") (pinfunction "PWM13_20") (pintype "output"))
      (node (ref "R23") (pin "P$1") (pinfunction "1_P$1") (pintype "passive"))
    )
    (net (code "53") (name "/PWM14") (class "Default")
      (node (ref "PCA9685") (pin "21") (pinfunction "PWM14_21") (pintype "output"))
      (node (ref "R24") (pin "P$1") (pinfunction "1_P$1") (pintype "passive"))
    )
    (net (code "54") (name "/PWM15") (class "Default")
      (node (ref "PCA9685") (pin "22") (pinfunction "PWM15_22") (pintype "output"))
      (node (ref "R25") (pin "P$1") (pinfunction "1_P$1") (pintype "passive"))
    )
    (net (code "55") (name "/RED_LED") (class "Default")
      (node (ref "D6") (pin "A") (pinfunction "A_A") (pintype "passive"))
      (node (ref "U3") (pin "20/A6") (pinfunction "20/A6/PWM_20/A6") (pintype "bidirectional"))
    )
    (net (code "56") (name "/RX1") (class "Default")
      (node (ref "J7") (pin "1") (pinfunction "1_1") (pintype "passive"))
      (node (ref "U3") (pin "0") (pinfunction "0/RX1/MOSI1_0") (pintype "bidirectional"))
    )
    (net (code "57") (name "/RX2") (class "Default")
      (node (ref "J3") (pin "3") (pinfunction "3_3") (pintype "passive"))
      (node (ref "U3") (pin "9") (pinfunction "9/RX2/PWM_9") (pintype "bidirectional"))
    )
    (net (code "58") (name "/RX3") (class "Default")
      (node (ref "J4") (pin "4") (pinfunction "4_4") (pintype "passive"))
      (node (ref "U3") (pin "7") (pinfunction "7/RX3/PWM_7") (pintype "bidirectional"))
      (node (ref "U9") (pin "TX") (pinfunction "TX_TX") (pintype "bidirectional"))
    )
    (net (code "59") (name "/SCK") (class "Default")
      (node (ref "J5") (pin "1") (pinfunction "1_1") (pintype "passive"))
      (node (ref "U3") (pin "13") (pinfunction "13/SCK0/LED_13") (pintype "bidirectional"))
      (node (ref "U8") (pin "5") (pinfunction "SCK_5") (pintype "bidirectional"))
    )
    (net (code "60") (name "/SCL") (class "Default")
      (node (ref "PCA9685") (pin "26") (pinfunction "SCL_26") (pintype "bidirectional"))
      (node (ref "R31") (pin "P$1") (pinfunction "1_P$1") (pintype "passive"))
      (node (ref "SCL") (pin "1") (pinfunction "1_1") (pintype "passive"))
      (node (ref "U3") (pin "19/A5") (pinfunction "19/A5/SCL0_19/A5") (pintype "bidirectional"))
      (node (ref "U5") (pin "SCL") (pinfunction "SCL_SCL") (pintype "bidirectional"))
      (node (ref "U6") (pin "SCL") (pinfunction "SCL_SCL") (pintype "bidirectional"))
    )
    (net (code "61") (name "/SDA") (class "Default")
      (node (ref "PCA9685") (pin "27") (pinfunction "SDA_27") (pintype "bidirectional"))
      (node (ref "R30") (pin "P$1") (pinfunction "1_P$1") (pintype "passive"))
      (node (ref "SDA") (pin "1") (pinfunction "1_1") (pintype "passive"))
      (node (ref "U3") (pin "18/A4") (pinfunction "18/A4/SDA0_18/A4") (pintype "bidirectional"))
      (node (ref "U5") (pin "SDA") (pinfunction "SDA_SDA") (pintype "bidirectional"))
      (node (ref "U6") (pin "SDA") (pinfunction "SDA_SDA") (pintype "bidirectional"))
    )
    (net (code "62") (name "/TX1") (class "Default")
      (node (ref "J7") (pin "2") (pinfunction "2_2") (pintype "passive"))
      (node (ref "U3") (pin "1") (pinfunction "1/TX1/MISO1_1") (pintype "bidirectional"))
    )
    (net (code "63") (name "/TX2") (class "Default")
      (node (ref "J3") (pin "2") (pinfunction "2_2") (pintype "passive"))
      (node (ref "J5") (pin "4") (pinfunction "4_4") (pintype "passive"))
      (node (ref "U3") (pin "10") (pinfunction "10/TX2/PWM_10") (pintype "bidirectional"))
      (node (ref "U8") (pin "8") (pinfunction "CS_8") (pintype "bidirectional"))
    )
    (net (code "64") (name "/TX3") (class "Default")
      (node (ref "J4") (pin "3") (pinfunction "3_3") (pintype "passive"))
      (node (ref "U3") (pin "8") (pinfunction "8/TX3/PWM_8") (pintype "bidirectional"))
      (node (ref "U9") (pin "RX") (pinfunction "RX_RX") (pintype "bidirectional"))
    )
    (net (code "65") (name "/VUSB") (class "Default")
      (node (ref "J11") (pin "3") (pinfunction "3_3") (pintype "passive"))
      (node (ref "U3") (pin "VUSB") (pinfunction "VUSB_VUSB") (pintype "power_in"))
    )
    (net (code "66") (name "/WHITE_LED") (class "Default")
      (node (ref "D3") (pin "A") (pinfunction "A_A") (pintype "passive"))
      (node (ref "U3") (pin "23/A9") (pinfunction "23/A9/PWM_23/A9") (pintype "bidirectional"))
    )
    (net (code "67") (name "/YELLOW_LED") (class "Default")
      (node (ref "D2") (pin "A") (pinfunction "A_A") (pintype "passive"))
      (node (ref "U3") (pin "22/A8") (pinfunction "22/A8/PWM_22/A8") (pintype "bidirectional"))
    )
    (net (code "68") (name "Net-(D1-C)") (class "Default")
      (node (ref "D1") (pin "K") (pinfunction "C_K") (pintype "passive"))
      (node (ref "R2") (pin "P$2") (pinfunction "2_P$2") (pintype "passive"))
    )
    (net (code "69") (name "Net-(D2-C)") (class "Default")
      (node (ref "D2") (pin "K") (pinfunction "C_K") (pintype "passive"))
      (node (ref "R3") (pin "P$2") (pinfunction "2_P$2") (pintype "passive"))
    )
    (net (code "70") (name "Net-(D3-C)") (class "Default")
      (node (ref "D3") (pin "K") (pinfunction "C_K") (pintype "passive"))
      (node (ref "R5") (pin "P$2") (pinfunction "2_P$2") (pintype "passive"))
    )
    (net (code "71") (name "Net-(D4-C)") (class "Default")
      (node (ref "D4") (pin "K") (pinfunction "C_K") (pintype "passive"))
      (node (ref "R4") (pin "P$2") (pinfunction "2_P$2") (pintype "passive"))
    )
    (net (code "72") (name "Net-(D6-C)") (class "Default")
      (node (ref "D6") (pin "K") (pinfunction "C_K") (pintype "passive"))
      (node (ref "R1") (pin "P$2") (pinfunction "2_P$2") (pintype "passive"))
    )
    (net (code "73") (name "Net-(G1-P)") (class "Default")
      (node (ref "G1") (pin "1") (pinfunction "P_1") (pintype "passive"))
      (node (ref "U8") (pin "10") (pinfunction "G1_10") (pintype "bidirectional"))
    )
    (net (code "74") (name "Net-(G2-P)") (class "Default")
      (node (ref "G2") (pin "1") (pinfunction "P_1") (pintype "passive"))
      (node (ref "U8") (pin "11") (pinfunction "G2_11") (pintype "bidirectional"))
    )
    (net (code "75") (name "Net-(G3-P)") (class "Default")
      (node (ref "G3") (pin "1") (pinfunction "P_1") (pintype "passive"))
      (node (ref "U8") (pin "12") (pinfunction "G3_12") (pintype "bidirectional"))
    )
    (net (code "76") (name "Net-(G4-P)") (class "Default")
      (node (ref "G4") (pin "1") (pinfunction "P_1") (pintype "passive"))
      (node (ref "U8") (pin "13") (pinfunction "G4_13") (pintype "bidirectional"))
    )
    (net (code "77") (name "Net-(G5-P)") (class "Default")
      (node (ref "G5") (pin "1") (pinfunction "P_1") (pintype "passive"))
      (node (ref "U8") (pin "14") (pinfunction "G5_14") (pintype "bidirectional"))
    )
    (net (code "78") (name "Net-(PCA9685-#OE)") (class "Default")
      (node (ref "PCA9685") (pin "23") (pinfunction "#OE_23") (pintype "input"))
      (node (ref "R36") (pin "P$1") (pinfunction "1_P$1") (pintype "passive"))
    )
    (net (code "79") (name "Net-(PCA9685-A0)") (class "Default")
      (node (ref "PCA9685") (pin "1") (pinfunction "A0_1") (pintype "bidirectional"))
      (node (ref "R28") (pin "P$1") (pinfunction "1_P$1") (pintype "passive"))
    )
    (net (code "80") (name "Net-(PCA9685-A1)") (class "Default")
      (node (ref "PCA9685") (pin "2") (pinfunction "A1_2") (pintype "bidirectional"))
      (node (ref "R29") (pin "P$1") (pinfunction "1_P$1") (pintype "passive"))
    )
    (net (code "81") (name "Net-(PCA9685-A2)") (class "Default")
      (node (ref "PCA9685") (pin "3") (pinfunction "A2_3") (pintype "bidirectional"))
      (node (ref "R32") (pin "P$1") (pinfunction "1_P$1") (pintype "passive"))
    )
    (net (code "82") (name "Net-(PCA9685-A3)") (class "Default")
      (node (ref "PCA9685") (pin "4") (pinfunction "A3_4") (pintype "bidirectional"))
      (node (ref "R35") (pin "P$2") (pinfunction "2_P$2") (pintype "passive"))
    )
    (net (code "83") (name "Net-(PCA9685-A4)") (class "Default")
      (node (ref "PCA9685") (pin "5") (pinfunction "A4_5") (pintype "bidirectional"))
      (node (ref "R34") (pin "P$2") (pinfunction "2_P$2") (pintype "passive"))
    )
    (net (code "84") (name "Net-(PCA9685-A5)") (class "Default")
      (node (ref "PCA9685") (pin "24") (pinfunction "A5_24") (pintype "bidirectional"))
      (node (ref "R33") (pin "P$2") (pinfunction "2_P$2") (pintype "passive"))
    )
    (net (code "85") (name "Net-(R10-2)") (class "Default")
      (node (ref "JP1") (pin "1") (pinfunction "1_1") (pintype "passive"))
      (node (ref "R10") (pin "P$2") (pinfunction "2_P$2") (pintype "passive"))
    )
    (net (code "86") (name "Net-(R11-2)") (class "Default")
      (node (ref "JP2") (pin "1") (pinfunction "1_1") (pintype "passive"))
      (node (ref "R11") (pin "P$2") (pinfunction "2_P$2") (pintype "passive"))
    )
    (net (code "87") (name "Net-(R12-2)") (class "Default")
      (node (ref "JP3") (pin "1") (pinfunction "1_1") (pintype "passive"))
      (node (ref "R12") (pin "P$2") (pinfunction "2_P$2") (pintype "passive"))
    )
    (net (code "88") (name "Net-(R13-2)") (class "Default")
      (node (ref "JP4") (pin "1") (pinfunction "1_1") (pintype "passive"))
      (node (ref "R13") (pin "P$2") (pinfunction "2_P$2") (pintype "passive"))
    )
    (net (code "89") (name "Net-(R14-2)") (class "Default")
      (node (ref "JP5") (pin "1") (pinfunction "1_1") (pintype "passive"))
      (node (ref "R14") (pin "P$2") (pinfunction "2_P$2") (pintype "passive"))
    )
    (net (code "90") (name "Net-(R15-2)") (class "Default")
      (node (ref "JP6") (pin "1") (pinfunction "1_1") (pintype "passive"))
      (node (ref "R15") (pin "P$2") (pinfunction "2_P$2") (pintype "passive"))
    )
    (net (code "91") (name "Net-(R16-2)") (class "Default")
      (node (ref "JP7") (pin "1") (pinfunction "1_1") (pintype "passive"))
      (node (ref "R16") (pin "P$2") (pinfunction "2_P$2") (pintype "passive"))
    )
    (net (code "92") (name "Net-(R17-2)") (class "Default")
      (node (ref "JP8") (pin "1") (pinfunction "1_1") (pintype "passive"))
      (node (ref "R17") (pin "P$2") (pinfunction "2_P$2") (pintype "passive"))
    )
    (net (code "93") (name "Net-(R18-2)") (class "Default")
      (node (ref "JP9") (pin "1") (pinfunction "1_1") (pintype "passive"))
      (node (ref "R18") (pin "P$2") (pinfunction "2_P$2") (pintype "passive"))
    )
    (net (code "94") (name "Net-(R19-2)") (class "Default")
      (node (ref "JP10") (pin "1") (pinfunction "1_1") (pintype "passive"))
      (node (ref "R19") (pin "P$2") (pinfunction "2_P$2") (pintype "passive"))
    )
    (net (code "95") (name "Net-(R20-2)") (class "Default")
      (node (ref "JP11") (pin "1") (pinfunction "1_1") (pintype "passive"))
      (node (ref "R20") (pin "P$2") (pinfunction "2_P$2") (pintype "passive"))
    )
    (net (code "96") (name "Net-(R21-2)") (class "Default")
      (node (ref "JP12") (pin "1") (pinfunction "1_1") (pintype "passive"))
      (node (ref "R21") (pin "P$2") (pinfunction "2_P$2") (pintype "passive"))
    )
    (net (code "97") (name "Net-(R22-2)") (class "Default")
      (node (ref "JP13") (pin "1") (pinfunction "1_1") (pintype "passive"))
      (node (ref "R22") (pin "P$2") (pinfunction "2_P$2") (pintype "passive"))
    )
    (net (code "98") (name "Net-(R23-2)") (class "Default")
      (node (ref "JP14") (pin "1") (pinfunction "1_1") (pintype "passive"))
      (node (ref "R23") (pin "P$2") (pinfunction "2_P$2") (pintype "passive"))
    )
    (net (code "99") (name "Net-(R24-2)") (class "Default")
      (node (ref "JP15") (pin "1") (pinfunction "1_1") (pintype "passive"))
      (node (ref "R24") (pin "P$2") (pinfunction "2_P$2") (pintype "passive"))
    )
    (net (code "100") (name "Net-(R25-2)") (class "Default")
      (node (ref "JP16") (pin "1") (pinfunction "1_1") (pintype "passive"))
      (node (ref "R25") (pin "P$2") (pinfunction "2_P$2") (pintype "passive"))
    )
    (net (code "101") (name "Net-(R27-2)") (class "Default")
      (node (ref "J1") (pin "3") (pinfunction "3_3") (pintype "passive"))
      (node (ref "R27") (pin "P$2") (pinfunction "2_P$2") (pintype "passive"))
    )
    (net (code "102") (name "unconnected-(U5-PadAUXCL)") (class "Default")
      (node (ref "U5") (pin "AUXCL") (pinfunction "AUXCL_AUXCL") (pintype "bidirectional"))
    )
    (net (code "103") (name "unconnected-(U5-PadAUXDA)") (class "Default")
      (node (ref "U5") (pin "AUXDA") (pinfunction "AUXDA_AUXDA") (pintype "bidirectional"))
    )
    (net (code "104") (name "unconnected-(U5-PadCS)") (class "Default")
      (node (ref "U5") (pin "CS") (pinfunction "CS_CS") (pintype "bidirectional"))
    )
    (net (code "105") (name "unconnected-(U5-PadVDDIO)") (class "Default")
      (node (ref "U5") (pin "VDDIO") (pinfunction "VDDIO_VDDIO") (pintype "bidirectional"))
    )
    (net (code "106") (name "unconnected-(U6-Pad3VO)") (class "Default")
      (node (ref "U6") (pin "3VO") (pinfunction "3VO_3VO") (pintype "bidirectional"))
    )
    (net (code "107") (name "unconnected-(U9-Pad3.3V)") (class "Default")
      (node (ref "U9") (pin "3.3V") (pinfunction "3.3V_3.3V") (pintype "bidirectional"))
    )
    (net (code "108") (name "unconnected-(U9-PadVBAT)") (class "Default")
      (node (ref "U9") (pin "VBAT") (pinfunction "VBAT_VBAT") (pintype "bidirectional"))
    )
  )
)
